# cw312_sam4s_cardedge.net
KiCad netlist of a schematic drawn in Altium Designer
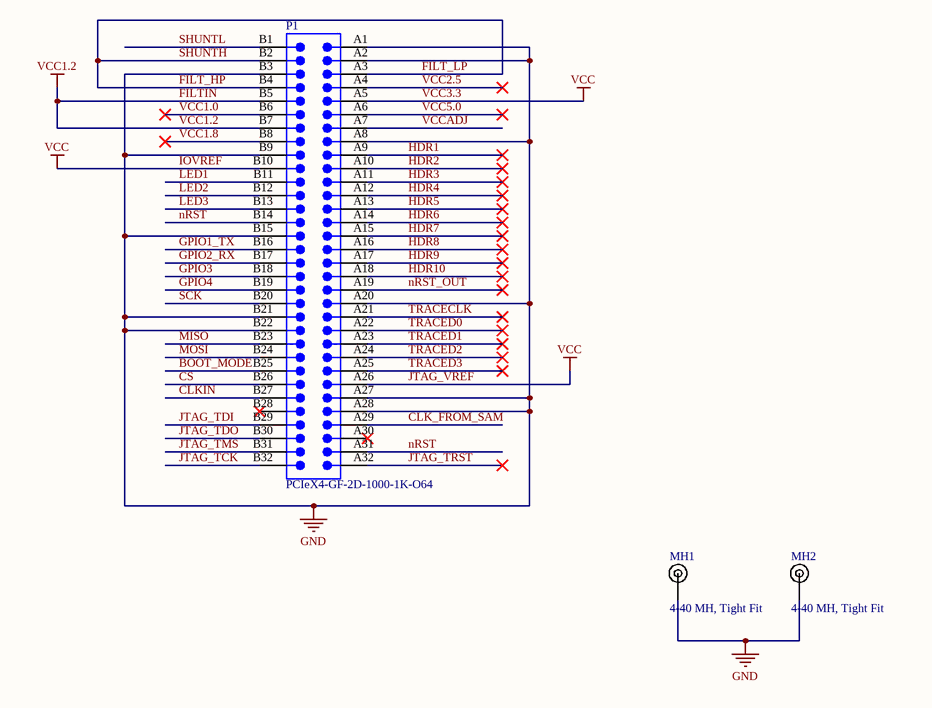
[diagram p0: cw312_sam4s_cardedge.SchDoc]

(export (version "E")
  (design (tool "Eeschema 10.0.6"))
  (components
    (comp (ref "MH1")
      (value "4-40 MH, Tight Fit")
      (footprint "MOUNT_#4_TIGHT")
      (description "Machine screw 4-40 Mounting Hole")
      (fields (field (name "PART NUMBER") "MOUNT_#4_TIGHT"))
      (libsource (lib "NewAE_AltiumLib") (part "Mounting_Hole"))
    )
    (comp (ref "MH2")
      (value "4-40 MH, Tight Fit")
      (footprint "MOUNT_#4_TIGHT")
      (description "Machine screw 4-40 Mounting Hole")
      (fields (field (name "PART NUMBER") "MOUNT_#4_TIGHT"))
      (libsource (lib "NewAE_AltiumLib") (part "Mounting_Hole"))
    )
    (comp (ref "P1")
      (value "PCIeX4-GF-2D-1000-1K-O64")
      (footprint "PCIeX4-GF-2D-1000-1K-O64")
      (description "Golden finger, PCIeX4, Dual, Opposite, Pitch 1mm, 64-Position")
      (fields (field (name "PUBLISHER") "Altium"))
      (libsource (lib "Altium Content Vault") (part "PCIeX4-GF-2D-1000-1K-O64"))
    )
  )
  (nets
    (net (code "1") (name "/BOOT_MODE") (class "Default")
      (node (ref "P1") (pin "B25") (pinfunction "B25_B25") (pintype "passive"))
    )
    (net (code "2") (name "/CLKIN") (class "Default")
      (node (ref "P1") (pin "B27") (pinfunction "B27_B27") (pintype "passive"))
    )
    (net (code "3") (name "/CLK_FROM_SAM") (class "Default")
      (node (ref "P1") (pin "A29") (pinfunction "A29_A29") (pintype "passive"))
    )
    (net (code "4") (name "/CS") (class "Default")
      (node (ref "P1") (pin "B26") (pinfunction "B26_B26") (pintype "passive"))
    )
    (net (code "5") (name "/FILT_HP") (class "Default")
      (node (ref "P1") (pin "A3") (pinfunction "A3_A3") (pintype "passive"))
      (node (ref "P1") (pin "B2") (pinfunction "B2_B2") (pintype "passive"))
      (node (ref "P1") (pin "B4") (pinfunction "B4_B4") (pintype "passive"))
    )
    (net (code "6") (name "/GPIO1_TX") (class "Default")
      (node (ref "P1") (pin "B16") (pinfunction "B16_B16") (pintype "passive"))
    )
    (net (code "7") (name "/GPIO2_RX") (class "Default")
      (node (ref "P1") (pin "B17") (pinfunction "B17_B17") (pintype "passive"))
    )
    (net (code "8") (name "/GPIO3") (class "Default")
      (node (ref "P1") (pin "B18") (pinfunction "B18_B18") (pintype "passive"))
    )
    (net (code "9") (name "/GPIO4") (class "Default")
      (node (ref "P1") (pin "B19") (pinfunction "B19_B19") (pintype "passive"))
    )
    (net (code "10") (name "/HDR1") (class "Default")
      (node (ref "P1") (pin "A9") (pinfunction "A9_A9") (pintype "passive+no_connect"))
    )
    (net (code "11") (name "/HDR2") (class "Default")
      (node (ref "P1") (pin "A10") (pinfunction "A10_A10") (pintype "passive+no_connect"))
    )
    (net (code "12") (name "/HDR3") (class "Default")
      (node (ref "P1") (pin "A11") (pinfunction "A11_A11") (pintype "passive+no_connect"))
    )
    (net (code "13") (name "/HDR4") (class "Default")
      (node (ref "P1") (pin "A12") (pinfunction "A12_A12") (pintype "passive+no_connect"))
    )
    (net (code "14") (name "/HDR5") (class "Default")
      (node (ref "P1") (pin "A13") (pinfunction "A13_A13") (pintype "passive+no_connect"))
    )
    (net (code "15") (name "/HDR6") (class "Default")
      (node (ref "P1") (pin "A14") (pinfunction "A14_A14") (pintype "passive+no_connect"))
    )
    (net (code "16") (name "/HDR7") (class "Default")
      (node (ref "P1") (pin "A15") (pinfunction "A15_A15") (pintype "passive+no_connect"))
    )
    (net (code "17") (name "/HDR8") (class "Default")
      (node (ref "P1") (pin "A16") (pinfunction "A16_A16") (pintype "passive+no_connect"))
    )
    (net (code "18") (name "/HDR9") (class "Default")
      (node (ref "P1") (pin "A17") (pinfunction "A17_A17") (pintype "passive+no_connect"))
    )
    (net (code "19") (name "/HDR10") (class "Default")
      (node (ref "P1") (pin "A18") (pinfunction "A18_A18") (pintype "passive+no_connect"))
    )
    (net (code "20") (name "/JTAG_TCK") (class "Default")
      (node (ref "P1") (pin "B32") (pinfunction "B32_B32") (pintype "passive"))
    )
    (net (code "21") (name "/JTAG_TDI") (class "Default")
      (node (ref "P1") (pin "B29") (pinfunction "B29_B29") (pintype "passive"))
    )
    (net (code "22") (name "/JTAG_TDO") (class "Default")
      (node (ref "P1") (pin "B30") (pinfunction "B30_B30") (pintype "passive"))
    )
    (net (code "23") (name "/JTAG_TMS") (class "Default")
      (node (ref "P1") (pin "B31") (pinfunction "B31_B31") (pintype "passive"))
    )
    (net (code "24") (name "/JTAG_TRST") (class "Default")
      (node (ref "P1") (pin "A32") (pinfunction "A32_A32") (pintype "passive+no_connect"))
    )
    (net (code "25") (name "/LED1") (class "Default")
      (node (ref "P1") (pin "B11") (pinfunction "B11_B11") (pintype "passive"))
    )
    (net (code "26") (name "/LED2") (class "Default")
      (node (ref "P1") (pin "B12") (pinfunction "B12_B12") (pintype "passive"))
    )
    (net (code "27") (name "/LED3") (class "Default")
      (node (ref "P1") (pin "B13") (pinfunction "B13_B13") (pintype "passive"))
    )
    (net (code "28") (name "/MISO") (class "Default")
      (node (ref "P1") (pin "B23") (pinfunction "B23_B23") (pintype "passive"))
    )
    (net (code "29") (name "/MOSI") (class "Default")
      (node (ref "P1") (pin "B24") (pinfunction "B24_B24") (pintype "passive"))
    )
    (net (code "30") (name "/SCK") (class "Default")
      (node (ref "P1") (pin "B20") (pinfunction "B20_B20") (pintype "passive"))
    )
    (net (code "31") (name "/SHUNTL") (class "Default")
      (node (ref "P1") (pin "B1") (pinfunction "B1_B1") (pintype "passive"))
    )
    (net (code "32") (name "/TRACECLK") (class "Default")
      (node (ref "P1") (pin "A21") (pinfunction "A21_A21") (pintype "passive+no_connect"))
    )
    (net (code "33") (name "/TRACED0") (class "Default")
      (node (ref "P1") (pin "A22") (pinfunction "A22_A22") (pintype "passive+no_connect"))
    )
    (net (code "34") (name "/TRACED1") (class "Default")
      (node (ref "P1") (pin "A23") (pinfunction "A23_A23") (pintype "passive+no_connect"))
    )
    (net (code "35") (name "/TRACED2") (class "Default")
      (node (ref "P1") (pin "A24") (pinfunction "A24_A24") (pintype "passive+no_connect"))
    )
    (net (code "36") (name "/TRACED3") (class "Default")
      (node (ref "P1") (pin "A25") (pinfunction "A25_A25") (pintype "passive+no_connect"))
    )
    (net (code "37") (name "/VCC1.0") (class "Default")
      (node (ref "P1") (pin "B6") (pinfunction "B6_B6") (pintype "passive+no_connect"))
    )
    (net (code "38") (name "/VCC1.8") (class "Default")
      (node (ref "P1") (pin "B8") (pinfunction "B8_B8") (pintype "passive+no_connect"))
    )
    (net (code "39") (name "/VCC2.5") (class "Default")
      (node (ref "P1") (pin "A4") (pinfunction "A4_A4") (pintype "passive+no_connect"))
    )
    (net (code "40") (name "/VCC5.0") (class "Default")
      (node (ref "P1") (pin "A6") (pinfunction "A6_A6") (pintype "passive+no_connect"))
    )
    (net (code "41") (name "/VCCADJ") (class "Default")
      (node (ref "P1") (pin "A7") (pinfunction "A7_A7") (pintype "passive"))
    )
    (net (code "42") (name "/nRST") (class "Default")
      (node (ref "P1") (pin "A31") (pinfunction "A31_A31") (pintype "passive"))
      (node (ref "P1") (pin "B14") (pinfunction "B14_B14") (pintype "passive"))
    )
    (net (code "43") (name "/nRST_OUT") (class "Default")
      (node (ref "P1") (pin "A19") (pinfunction "A19_A19") (pintype "passive+no_connect"))
    )
    (net (code "44") (name "GND") (class "Default")
      (node (ref "MH1") (pin "1") (pinfunction "1_1") (pintype "passive"))
      (node (ref "MH2") (pin "1") (pinfunction "1_1") (pintype "passive"))
      (node (ref "P1") (pin "A1") (pinfunction "A1_A1") (pintype "passive"))
      (node (ref "P1") (pin "A2") (pinfunction "A2_A2") (pintype "passive"))
      (node (ref "P1") (pin "A20") (pinfunction "A20_A20") (pintype "passive"))
      (node (ref "P1") (pin "A27") (pinfunction "A27_A27") (pintype "passive"))
      (node (ref "P1") (pin "A28") (pinfunction "A28_A28") (pintype "passive"))
      (node (ref "P1") (pin "A8") (pinfunction "A8_A8") (pintype "passive"))
      (node (ref "P1") (pin "B15") (pinfunction "B15_B15") (pintype "passive"))
      (node (ref "P1") (pin "B21") (pinfunction "B21_B21") (pintype "passive"))
      (node (ref "P1") (pin "B22") (pinfunction "B22_B22") (pintype "passive"))
      (node (ref "P1") (pin "B3") (pinfunction "B3_B3") (pintype "passive"))
      (node (ref "P1") (pin "B9") (pinfunction "B9_B9") (pintype "passive"))
    )
    (net (code "45") (name "VCC") (class "Default")
      (node (ref "P1") (pin "A26") (pinfunction "A26_A26") (pintype "passive"))
      (node (ref "P1") (pin "A5") (pinfunction "A5_A5") (pintype "passive"))
      (node (ref "P1") (pin "B10") (pinfunction "B10_B10") (pintype "passive"))
    )
    (net (code "46") (name "VCC1.2") (class "Default")
      (node (ref "P1") (pin "B5") (pinfunction "B5_B5") (pintype "passive"))
      (node (ref "P1") (pin "B7") (pinfunction "B7_B7") (pintype "passive"))
    )
    (net (code "47") (name "unconnected-(P1-PadA30)") (class "Default")
      (node (ref "P1") (pin "A30") (pinfunction "A30_A30") (pintype "passive+no_connect"))
    )
    (net (code "48") (name "unconnected-(P1-PadB28)") (class "Default")
      (node (ref "P1") (pin "B28") (pinfunction "B28_B28") (pintype "passive+no_connect"))
    )
  )
)
